# adc-v5.net
KiCad netlist of a schematic drawn in Altium Designer
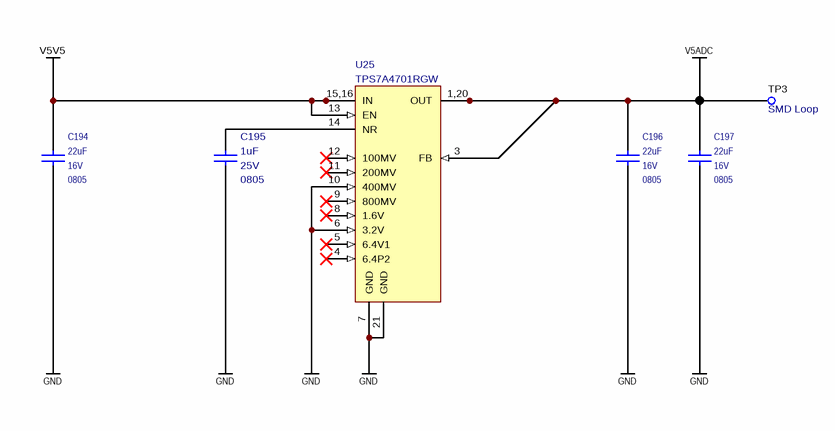
[diagram p0: adc-v5.SchDoc]

(export (version "E")
  (design (tool "Eeschema 10.0.6"))
  (components
    (comp (ref "C194")
      (value "22uF")
      (footprint "generic:CAPC200X125X145L45N")
      (description "Ceramic Capacitor 22uF ±10% 16V X5R 0805")
      (fields
        (field (name "MANUFACTURER") "TDK")
        (field (name "VOLTAGE") "16V")
        (field (name "PACKAGE") "0805")
        (field (name "TOLERANCE") "±10%")
      )
      (libsource (lib "generic") (part "CAP 0603"))
    )
    (comp (ref "C195")
      (value "1uF")
      (footprint "CAPC200X125X145L45N")
      (description "Ceramic Capacitor 1uF ±10% 25V X7R 0805")
      (fields
        (field (name "MANUFACTURER") "Taiyo Yuden")
        (field (name "TOLERANCE") "±10%")
        (field (name "PACKAGE") "0805")
        (field (name "VOLTAGE") "25V")
      )
      (libsource (lib "capacitors") (part "CAP"))
    )
    (comp (ref "C196")
      (value "22uF")
      (footprint "generic:CAPC200X125X145L45N")
      (description "Ceramic Capacitor 22uF ±10% 16V X5R 0805")
      (fields
        (field (name "MANUFACTURER") "TDK")
        (field (name "VOLTAGE") "16V")
        (field (name "PACKAGE") "0805")
        (field (name "TOLERANCE") "±10%")
      )
      (libsource (lib "generic") (part "CAP 0603"))
    )
    (comp (ref "C197")
      (value "22uF")
      (footprint "generic:CAPC200X125X145L45N")
      (description "Ceramic Capacitor 22uF ±10% 16V X5R 0805")
      (fields
        (field (name "MANUFACTURER") "TDK")
        (field (name "VOLTAGE") "16V")
        (field (name "PACKAGE") "0805")
        (field (name "TOLERANCE") "±10%")
      )
      (libsource (lib "generic") (part "CAP 0603"))
    )
    (comp (ref "TP3")
      (value "5015")
      (footprint "keystone:5015")
      (description "Test Point SMD")
      (fields (field (name "MANUFACTURER") "Keystone") (field (name "NOTES") "SMD Loop"))
      (libsource (lib "generic") (part "TEST_POINT_SMD_50"))
    )
    (comp (ref "U25")
      (value "TPS7A4701RGW")
      (footprint "QFN65P500X500X100-21N")
      (description "Low-Dropout Linear Regulator 20-VQFN")
      (fields (field (name "MANUFACTURER") "Texas Instruments"))
      (libsource (lib "ti") (part "TPS7A4701RGW_1"))
    )
  )
  (nets
    (net (code "1") (name "GND") (class "Default")
      (node (ref "C194") (pin "1") (pinfunction "1_1") (pintype "passive"))
      (node (ref "C195") (pin "2") (pinfunction "2_2") (pintype "passive"))
      (node (ref "C196") (pin "1") (pinfunction "1_1") (pintype "passive"))
      (node (ref "C197") (pin "1") (pinfunction "1_1") (pintype "passive"))
      (node (ref "U25") (pin "10") (pinfunction "400MV_10") (pintype "input"))
      (node (ref "U25") (pin "21") (pinfunction "GND_21") (pintype "power_in"))
      (node (ref "U25") (pin "6") (pinfunction "3.2V_6") (pintype "input"))
      (node (ref "U25") (pin "7") (pinfunction "GND_7") (pintype "power_in"))
    )
    (net (code "2") (name "Net-(U25-NR)") (class "Default")
      (node (ref "C195") (pin "1") (pinfunction "1_1") (pintype "passive"))
      (node (ref "U25") (pin "14") (pinfunction "NR_14") (pintype "passive"))
    )
    (net (code "3") (name "V5ADC") (class "Default")
      (node (ref "C196") (pin "2") (pinfunction "2_2") (pintype "passive"))
      (node (ref "C197") (pin "2") (pinfunction "2_2") (pintype "passive"))
      (node (ref "TP3") (pin "1") (pinfunction "1_1") (pintype "passive"))
      (node (ref "U25") (pin "1") (pinfunction "OUT_1") (pintype "passive"))
      (node (ref "U25") (pin "20") (pinfunction "OUT_20") (pintype "passive"))
      (node (ref "U25") (pin "3") (pinfunction "FB_3") (pintype "input"))
    )
    (net (code "4") (name "V5V5") (class "Default")
      (node (ref "C194") (pin "2") (pinfunction "2_2") (pintype "passive"))
      (node (ref "U25") (pin "13") (pinfunction "EN_13") (pintype "input"))
      (node (ref "U25") (pin "15") (pinfunction "IN_15") (pintype "passive"))
      (node (ref "U25") (pin "16") (pinfunction "IN_16") (pintype "passive"))
    )
    (net (code "5") (name "unconnected-(U25-1.6V-Pad8)") (class "Default")
      (node (ref "U25") (pin "8") (pinfunction "1.6V_8") (pintype "input+no_connect"))
    )
    (net (code "6") (name "unconnected-(U25-6.4P2-Pad4)") (class "Default")
      (node (ref "U25") (pin "4") (pinfunction "6.4P2_4") (pintype "input+no_connect"))
    )
    (net (code "7") (name "unconnected-(U25-6.4V1-Pad5)") (class "Default")
      (node (ref "U25") (pin "5") (pinfunction "6.4V1_5") (pintype "input+no_connect"))
    )
    (net (code "8") (name "unconnected-(U25-100MV-Pad12)") (class "Default")
      (node (ref "U25") (pin "12") (pinfunction "100MV_12") (pintype "input+no_connect"))
    )
    (net (code "9") (name "unconnected-(U25-200MV-Pad11)") (class "Default")
      (node (ref "U25") (pin "11") (pinfunction "200MV_11") (pintype "input+no_connect"))
    )
    (net (code "10") (name "unconnected-(U25-800MV-Pad9)") (class "Default")
      (node (ref "U25") (pin "9") (pinfunction "800MV_9") (pintype "input+no_connect"))
    )
  )
)
